# ESP8266_v2.net
KiCad netlist of a schematic drawn in EAGLE
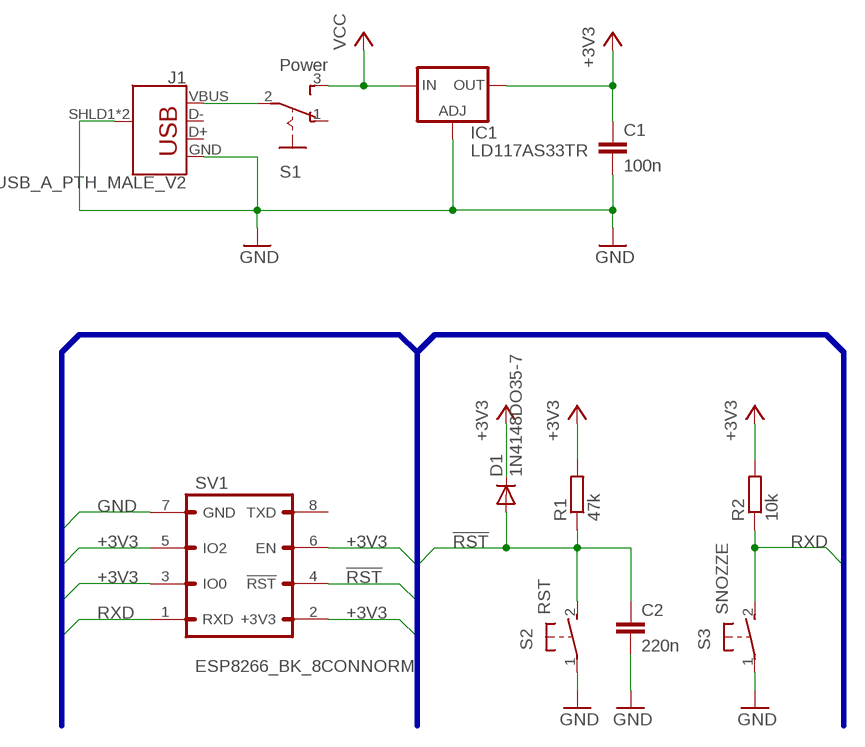
[diagram p0: schematic, sheet 1]

(export (version "E")
  (design (tool "Eeschema 10.0.6"))
  (components
    (comp (ref "C1")
      (value "100n")
      (footprint "eagle-import:C050-025X075")
      (libsource (lib "eagle-import") (part "C-EU050-025X075"))
    )
    (comp (ref "C2")
      (value "220n")
      (footprint "eagle-import:C050-025X075")
      (libsource (lib "eagle-import") (part "C-EU050-025X075"))
    )
    (comp (ref "D1")
      (value "1N4148DO35-7")
      (footprint "eagle-import:DO35-7")
      (libsource (lib "eagle-import") (part "1N4148DO35-7"))
    )
    (comp (ref "IC1")
      (value "LD117AS33TR")
      (footprint "eagle-import:SOT223")
      (libsource (lib "eagle-import") (part "LD117A?S33TR"))
    )
    (comp (ref "J1")
      (value "USB_A_PTH_MALE_V2")
      (footprint "eagle-import:USB-A-H-V2")
      (libsource (lib "eagle-import") (part "USB_A_PTH_MALE_V2"))
    )
    (comp (ref "R1")
      (value "47k")
      (footprint "eagle-import:0204_5")
      (libsource (lib "eagle-import") (part "R-EU_0204/5"))
    )
    (comp (ref "R2")
      (value "10k")
      (footprint "eagle-import:0204_5")
      (libsource (lib "eagle-import") (part "R-EU_0204/5"))
    )
    (comp (ref "S1")
      (value "Power")
      (footprint "eagle-import:255SB-B")
      (libsource (lib "eagle-import") (part "255SBSMALL-H"))
    )
    (comp (ref "S2")
      (value "RST")
      (footprint "eagle-import:DT6-1")
      (libsource (lib "eagle-import") (part "SWITCH_2PIN"))
    )
    (comp (ref "S3")
      (value "SNOZZE")
      (footprint "eagle-import:DT6-1")
      (libsource (lib "eagle-import") (part "SWITCH_2PIN"))
    )
    (comp (ref "SV1")
      (value "ESP8266_BK_8CONNORM")
      (footprint "eagle-import:ESP8266_8CON")
      (libsource (lib "eagle-import") (part "ESP8266_BK_8CONNORM"))
    )
  )
  (nets
    (net (code "1") (name "+3V3") (class "Default")
      (node (ref "C1") (pin "1") (pinfunction "1_1") (pintype "passive"))
      (node (ref "D1") (pin "C") (pinfunction "C_C") (pintype "passive"))
      (node (ref "IC1") (pin "2") (pinfunction "OUT_2") (pintype "passive"))
      (node (ref "IC1") (pin "4") (pinfunction "OUT_4") (pintype "passive"))
      (node (ref "R1") (pin "2") (pinfunction "2_2") (pintype "passive"))
      (node (ref "R2") (pin "2") (pinfunction "2_2") (pintype "passive"))
      (node (ref "SV1") (pin "2") (pinfunction "+3V3_2") (pintype "passive"))
      (node (ref "SV1") (pin "3") (pinfunction "IO0_3") (pintype "passive"))
      (node (ref "SV1") (pin "5") (pinfunction "IO2_5") (pintype "passive"))
      (node (ref "SV1") (pin "6") (pinfunction "EN_6") (pintype "passive"))
    )
    (net (code "2") (name "/RXD") (class "Default")
      (node (ref "R2") (pin "1") (pinfunction "1_1") (pintype "passive"))
      (node (ref "S3") (pin "2") (pinfunction "S_2") (pintype "passive"))
      (node (ref "SV1") (pin "1") (pinfunction "RXD_1") (pintype "passive"))
    )
    (net (code "3") (name "/~{RST}") (class "Default")
      (node (ref "C2") (pin "1") (pinfunction "1_1") (pintype "passive"))
      (node (ref "D1") (pin "A") (pinfunction "A_A") (pintype "passive"))
      (node (ref "R1") (pin "1") (pinfunction "1_1") (pintype "passive"))
      (node (ref "S2") (pin "2") (pinfunction "S_2") (pintype "passive"))
      (node (ref "SV1") (pin "4") (pinfunction "~{RST}_4") (pintype "passive"))
    )
    (net (code "4") (name "GND") (class "Default")
      (node (ref "C1") (pin "2") (pinfunction "2_2") (pintype "passive"))
      (node (ref "C2") (pin "2") (pinfunction "2_2") (pintype "passive"))
      (node (ref "IC1") (pin "1") (pinfunction "ADJ_1") (pintype "input"))
      (node (ref "J1") (pin "GND") (pinfunction "GND_GND") (pintype "power_in"))
      (node (ref "J1") (pin "SHLD1") (pinfunction "SHIELD_SHLD1") (pintype "bidirectional"))
      (node (ref "J1") (pin "SHLD2") (pinfunction "SHIELD_SHLD2") (pintype "bidirectional"))
      (node (ref "S2") (pin "1") (pinfunction "P_1") (pintype "passive"))
      (node (ref "S3") (pin "1") (pinfunction "P_1") (pintype "passive"))
      (node (ref "SV1") (pin "7") (pinfunction "GND_7") (pintype "passive"))
    )
    (net (code "5") (name "Net-(S1-P)") (class "Default")
      (node (ref "J1") (pin "VBUS") (pinfunction "VBUS_VBUS") (pintype "power_in"))
      (node (ref "S1") (pin "2") (pinfunction "P_2") (pintype "passive"))
    )
    (net (code "6") (name "VCC") (class "Default")
      (node (ref "IC1") (pin "3") (pinfunction "IN_3") (pintype "input"))
      (node (ref "S1") (pin "3") (pinfunction "S_3") (pintype "passive"))
    )
    (net (code "7") (name "unconnected-(J1-PadD+)") (class "Default")
      (node (ref "J1") (pin "D+") (pinfunction "D+_D+") (pintype "bidirectional"))
    )
    (net (code "8") (name "unconnected-(J1-PadD-)") (class "Default")
      (node (ref "J1") (pin "D-") (pinfunction "D-_D-") (pintype "bidirectional"))
    )
    (net (code "9") (name "unconnected-(S1-O-Pad1)") (class "Default")
      (node (ref "S1") (pin "1") (pinfunction "O_1") (pintype "passive"))
    )
    (net (code "10") (name "unconnected-(SV1-TXD-Pad8)") (class "Default")
      (node (ref "SV1") (pin "8") (pinfunction "TXD_8") (pintype "passive"))
    )
  )
)
